# node.net
KiCad netlist of a schematic drawn in EAGLE
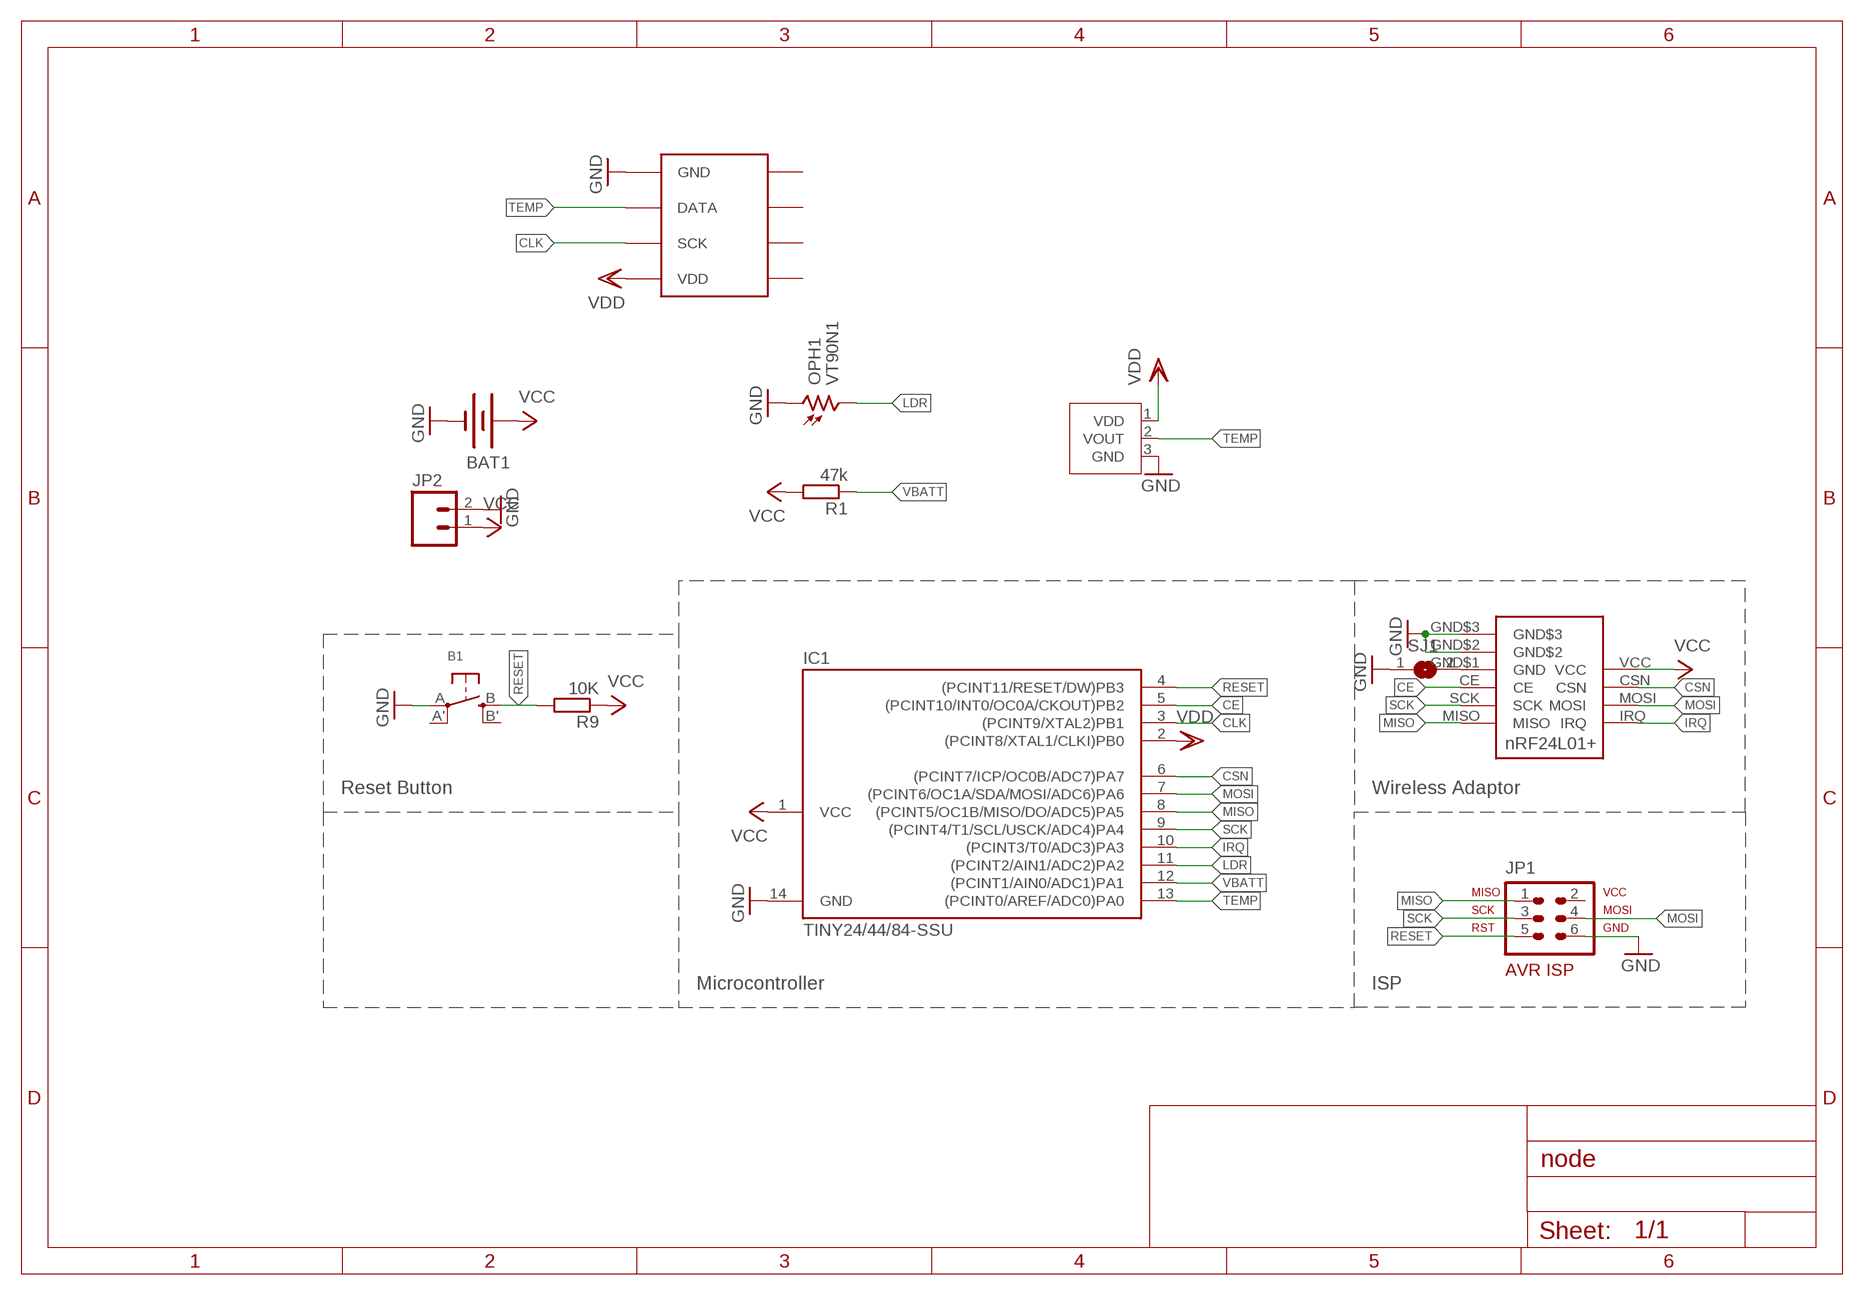
[diagram p0: schematic, sheet 1]

(export (version "E")
  (design (tool "Eeschema 10.0.6"))
  (components
    (comp (ref "B1")
      (value "SWITCH_TACT_SMT")
      (footprint "eagle-import:EVQ-Q2")
      (libsource (lib "eagle-import") (part "SWITCH_TACT_SMT"))
    )
    (comp (ref "BAT1")
      (value "BATTERY20SMD")
      (footprint "eagle-import:BATTCON_20MM")
      (libsource (lib "eagle-import") (part "BATTERY20SMD"))
    )
    (comp (ref "CHINESE1")
      (value "NRF24L01+CHINESE-DUAL")
      (footprint "eagle-import:CHINESE-DUALPINOUT")
      (libsource (lib "eagle-import") (part "NRF24L01+CHINESE-DUAL"))
    )
    (comp (ref "IC1")
      (value "TINY24/44/84-SSU")
      (footprint "eagle-import:SOIC14")
      (libsource (lib "eagle-import") (part "TINY24/44/84-SSU"))
    )
    (comp (ref "JP1")
      (value "AVR-ISP-6VERT")
      (footprint "eagle-import:AVR-ISP-6")
      (libsource (lib "eagle-import") (part "AVR-ISP-6VERT"))
    )
    (comp (ref "JP2")
      (value "M02POLAR_LOCK")
      (footprint "eagle-import:MOLEX-1X2_LOCK")
      (libsource (lib "eagle-import") (part "M02POLAR_LOCK"))
    )
    (comp (ref "OPH1")
      (value "VT90N1")
      (footprint "eagle-import:VT900")
      (libsource (lib "eagle-import") (part "VT90N1"))
    )
    (comp (ref "R1")
      (value "47k")
      (footprint "eagle-import:R0805")
      (libsource (lib "eagle-import") (part "R-EU_R0805"))
    )
    (comp (ref "R9")
      (value "10K")
      (footprint "eagle-import:R0805")
      (libsource (lib "eagle-import") (part "R-EU_R0805"))
    )
    (comp (ref "SHT1")
      (value "SHT11")
      (footprint "eagle-import:SHT11")
      (libsource (lib "eagle-import") (part "SHT11"))
    )
    (comp (ref "SJ1") (value "SJ") (footprint "eagle-import:SJ") (libsource (lib "eagle-import") (part "SJ")))
    (comp (ref "U$1")
      (value "MCP970XTT")
      (footprint "eagle-import:SOT23")
      (libsource (lib "eagle-import") (part "MCP970XTT"))
    )
  )
  (nets
    (net (code "1") (name "CE") (class "Default")
      (node (ref "CHINESE1") (pin "CE") (pinfunction "CE_CE") (pintype "bidirectional"))
      (node (ref "IC1") (pin "5") (pinfunction "(PCINT10/INT0/OC0A/CKOUT)PB2_5") (pintype "bidirectional"))
    )
    (net (code "2") (name "CLK") (class "Default")
      (node (ref "IC1") (pin "3") (pinfunction "(PCINT9/XTAL2)PB1_3") (pintype "bidirectional"))
      (node (ref "SHT1") (pin "SCK") (pinfunction "SCK_SCK") (pintype "input"))
    )
    (net (code "3") (name "CSN") (class "Default")
      (node (ref "CHINESE1") (pin "CSN") (pinfunction "CSN_CSN") (pintype "bidirectional"))
      (node (ref "IC1") (pin "6") (pinfunction "(PCINT7/ICP/OC0B/ADC7)PA7_6") (pintype "bidirectional"))
    )
    (net (code "4") (name "GND") (class "Default")
      (node (ref "B1") (pin "A") (pinfunction "P_A") (pintype "passive"))
      (node (ref "BAT1") (pin "2") (pinfunction "-_2") (pintype "power_in"))
      (node (ref "CHINESE1") (pin "GND$2") (pinfunction "GND$2_GND$2") (pintype "bidirectional"))
      (node (ref "CHINESE1") (pin "GND$3") (pinfunction "GND$3_GND$3") (pintype "bidirectional"))
      (node (ref "IC1") (pin "14") (pinfunction "GND_14") (pintype "power_in"))
      (node (ref "JP1") (pin "6") (pinfunction "6_6") (pintype "passive"))
      (node (ref "JP2") (pin "2") (pinfunction "2_2") (pintype "passive"))
      (node (ref "OPH1") (pin "1") (pinfunction "1_1") (pintype "passive"))
      (node (ref "SHT1") (pin "GND") (pinfunction "GND_GND") (pintype "power_in"))
      (node (ref "SJ1") (pin "1") (pinfunction "1_1") (pintype "passive"))
      (node (ref "U$1") (pin "3") (pinfunction "GND_3") (pintype "power_in"))
    )
    (net (code "5") (name "IRQ") (class "Default")
      (node (ref "CHINESE1") (pin "IRQ") (pinfunction "IRQ_IRQ") (pintype "bidirectional"))
      (node (ref "IC1") (pin "10") (pinfunction "(PCINT3/T0/ADC3)PA3_10") (pintype "bidirectional"))
    )
    (net (code "6") (name "LDR") (class "Default")
      (node (ref "IC1") (pin "11") (pinfunction "(PCINT2/AIN1/ADC2)PA2_11") (pintype "bidirectional"))
      (node (ref "OPH1") (pin "2") (pinfunction "2_2") (pintype "passive"))
    )
    (net (code "7") (name "MISO") (class "Default")
      (node (ref "CHINESE1") (pin "MISO") (pinfunction "MISO_MISO") (pintype "bidirectional"))
      (node (ref "IC1") (pin "8") (pinfunction "(PCINT5/OC1B/MISO/DO/ADC5)PA5_8") (pintype "bidirectional"))
      (node (ref "JP1") (pin "1") (pinfunction "1_1") (pintype "passive"))
    )
    (net (code "8") (name "MOSI") (class "Default")
      (node (ref "CHINESE1") (pin "MOSI") (pinfunction "MOSI_MOSI") (pintype "bidirectional"))
      (node (ref "IC1") (pin "7") (pinfunction "(PCINT6/OC1A/SDA/MOSI/ADC6)PA6_7") (pintype "bidirectional"))
      (node (ref "JP1") (pin "4") (pinfunction "4_4") (pintype "passive"))
    )
    (net (code "9") (name "Net-(CHINESE1-GND)") (class "Default")
      (node (ref "CHINESE1") (pin "GND$1") (pinfunction "GND_GND$1") (pintype "bidirectional"))
      (node (ref "SJ1") (pin "2") (pinfunction "2_2") (pintype "passive"))
    )
    (net (code "10") (name "RESET") (class "Default")
      (node (ref "B1") (pin "B") (pinfunction "S_B") (pintype "passive"))
      (node (ref "IC1") (pin "4") (pinfunction "(PCINT11/RESET/DW)PB3_4") (pintype "bidirectional"))
      (node (ref "JP1") (pin "5") (pinfunction "5_5") (pintype "passive"))
      (node (ref "R9") (pin "2") (pinfunction "2_2") (pintype "passive"))
    )
    (net (code "11") (name "SCK") (class "Default")
      (node (ref "CHINESE1") (pin "SCK") (pinfunction "SCK_SCK") (pintype "bidirectional"))
      (node (ref "IC1") (pin "9") (pinfunction "(PCINT4/T1/SCL/USCK/ADC4)PA4_9") (pintype "bidirectional"))
      (node (ref "JP1") (pin "3") (pinfunction "3_3") (pintype "passive"))
    )
    (net (code "12") (name "TEMP") (class "Default")
      (node (ref "IC1") (pin "13") (pinfunction "(PCINT0/AREF/ADC0)PA0_13") (pintype "bidirectional"))
      (node (ref "SHT1") (pin "DATA") (pinfunction "DATA_DATA") (pintype "bidirectional"))
      (node (ref "U$1") (pin "2") (pinfunction "VOUT_2") (pintype "output"))
    )
    (net (code "13") (name "VBATT") (class "Default")
      (node (ref "IC1") (pin "12") (pinfunction "(PCINT1/AIN0/ADC1)PA1_12") (pintype "bidirectional"))
      (node (ref "R1") (pin "1") (pinfunction "1_1") (pintype "passive"))
    )
    (net (code "14") (name "VCC") (class "Default")
      (node (ref "BAT1") (pin "1") (pinfunction "+_1") (pintype "power_in"))
      (node (ref "CHINESE1") (pin "VCC") (pinfunction "VCC_VCC") (pintype "bidirectional"))
      (node (ref "IC1") (pin "1") (pinfunction "VCC_1") (pintype "power_in"))
      (node (ref "JP2") (pin "1") (pinfunction "1_1") (pintype "passive"))
      (node (ref "R1") (pin "2") (pinfunction "2_2") (pintype "passive"))
      (node (ref "R9") (pin "1") (pinfunction "1_1") (pintype "passive"))
    )
    (net (code "15") (name "VDD") (class "Default")
      (node (ref "IC1") (pin "2") (pinfunction "(PCINT8/XTAL1/CLKI)PB0_2") (pintype "bidirectional"))
      (node (ref "SHT1") (pin "VDD") (pinfunction "VDD_VDD") (pintype "power_in"))
      (node (ref "U$1") (pin "1") (pinfunction "VDD_1") (pintype "power_in"))
    )
    (net (code "16") (name "unconnected-(B1-P1-PadA')") (class "Default")
      (node (ref "B1") (pin "A'") (pinfunction "P1_A'") (pintype "passive"))
    )
    (net (code "17") (name "unconnected-(B1-S1-PadB')") (class "Default")
      (node (ref "B1") (pin "B'") (pinfunction "S1_B'") (pintype "passive"))
    )
    (net (code "18") (name "unconnected-(JP1-Pad2)") (class "Default")
      (node (ref "JP1") (pin "2") (pinfunction "2_2") (pintype "passive"))
    )
    (net (code "19") (name "unconnected-(SHT1-Pad5)") (class "Default")
      (node (ref "SHT1") (pin "5") (pinfunction "5_5") (pintype "no_connect"))
    )
    (net (code "20") (name "unconnected-(SHT1-Pad6)") (class "Default")
      (node (ref "SHT1") (pin "6") (pinfunction "6_6") (pintype "no_connect"))
    )
    (net (code "21") (name "unconnected-(SHT1-Pad7)") (class "Default")
      (node (ref "SHT1") (pin "7") (pinfunction "7_7") (pintype "no_connect"))
    )
    (net (code "22") (name "unconnected-(SHT1-Pad8)") (class "Default")
      (node (ref "SHT1") (pin "8") (pinfunction "8_8") (pintype "no_connect"))
    )
  )
)
